# EVGP_Estop_Daugherboard_with_LED.net
KiCad netlist of a schematic drawn in EAGLE
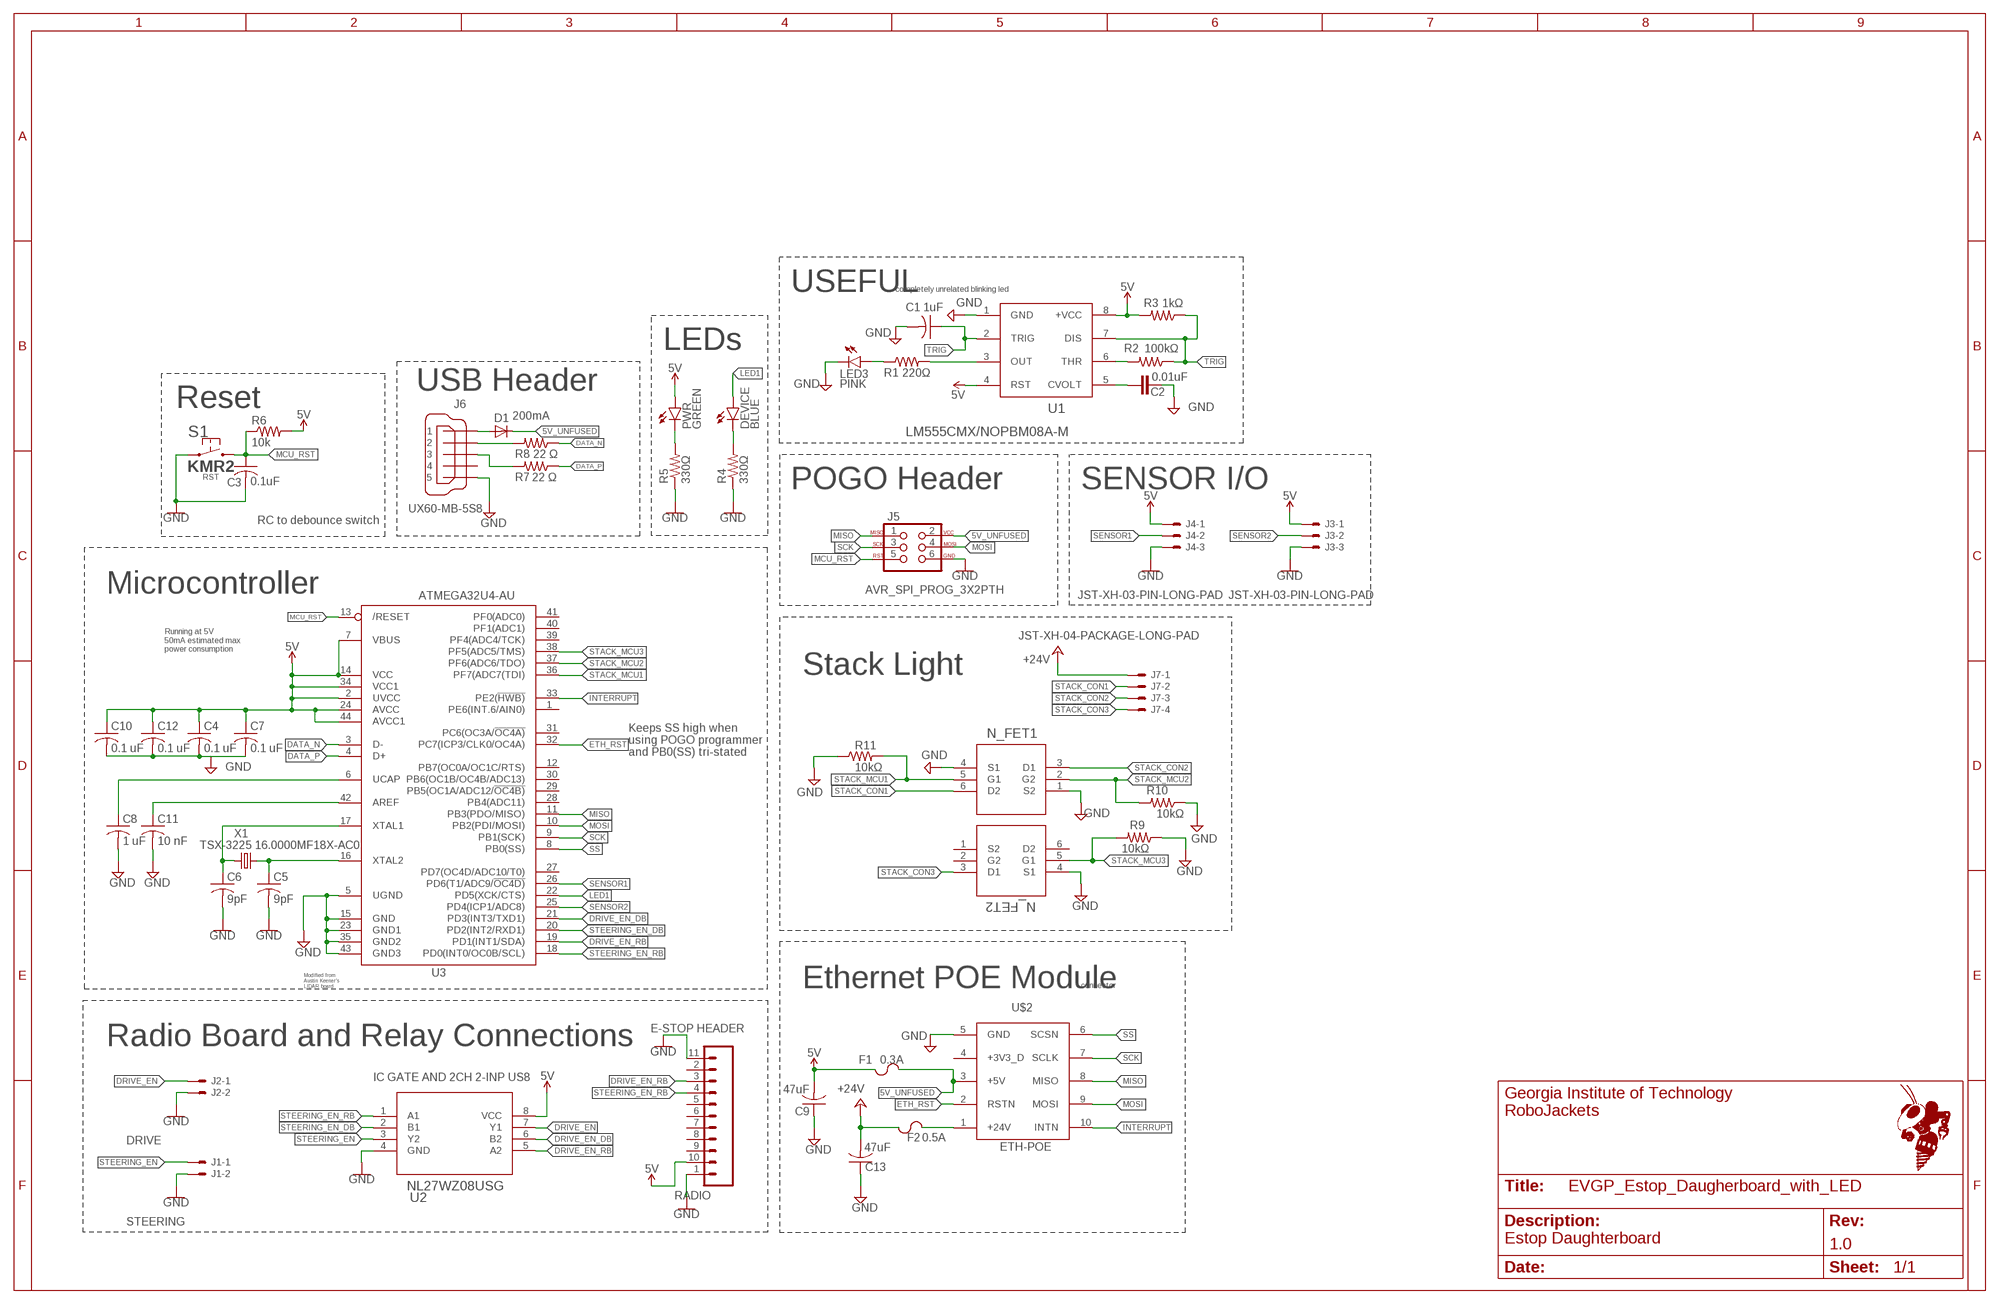
[diagram p0: schematic, sheet 1]

(export (version "E")
  (design (tool "Eeschema 10.0.6"))
  (components
    (comp (ref "C1")
      (value "1uF")
      (footprint "eagle-import:C1206")
      (libsource (lib "eagle-import") (part "C-USC1206"))
    )
    (comp (ref "C2")
      (value "0.01uF")
      (footprint "eagle-import:C0603")
      (libsource (lib "eagle-import") (part "C-EUC0603"))
    )
    (comp (ref "C3")
      (value "0.1uF")
      (footprint "eagle-import:C0603")
      (libsource (lib "eagle-import") (part "C-USC0603"))
    )
    (comp (ref "C4")
      (value "0.1 uF")
      (footprint "eagle-import:C0603")
      (libsource (lib "eagle-import") (part "resistor_348_C-USC0603"))
    )
    (comp (ref "C5")
      (value "9pF")
      (footprint "eagle-import:C0603")
      (libsource (lib "eagle-import") (part "resistor_348_C-USC0603"))
    )
    (comp (ref "C6")
      (value "9pF")
      (footprint "eagle-import:C0603")
      (libsource (lib "eagle-import") (part "resistor_348_C-USC0603"))
    )
    (comp (ref "C7")
      (value "0.1 uF")
      (footprint "eagle-import:C0603")
      (libsource (lib "eagle-import") (part "resistor_348_C-USC0603"))
    )
    (comp (ref "C8")
      (value "1 uF")
      (footprint "eagle-import:C0603")
      (libsource (lib "eagle-import") (part "resistor_348_C-USC0603"))
    )
    (comp (ref "C9")
      (value "47uF")
      (footprint "eagle-import:C1206")
      (libsource (lib "eagle-import") (part "C-USC1206"))
    )
    (comp (ref "C10")
      (value "0.1 uF")
      (footprint "eagle-import:C0603")
      (libsource (lib "eagle-import") (part "resistor_348_C-USC0603"))
    )
    (comp (ref "C11")
      (value "10 nF")
      (footprint "eagle-import:C0603")
      (libsource (lib "eagle-import") (part "resistor_348_C-USC0603"))
    )
    (comp (ref "C12")
      (value "0.1 uF")
      (footprint "eagle-import:C0603")
      (libsource (lib "eagle-import") (part "resistor_348_C-USC0603"))
    )
    (comp (ref "C13")
      (value "47uF")
      (footprint "eagle-import:C1206")
      (libsource (lib "eagle-import") (part "C-USC1206"))
    )
    (comp (ref "D1")
      (value "200mA")
      (footprint "eagle-import:SOD323-R")
      (libsource (lib "eagle-import") (part "DIODE-SOD323-R"))
    )
    (comp (ref "DEVICE")
      (value "BLUE")
      (footprint "eagle-import:CHIP-LED0603")
      (libsource (lib "eagle-import") (part "LEDCHIP-LED0603"))
    )
    (comp (ref "F1")
      (value "0.3A")
      (footprint "eagle-import:F1206")
      (libsource (lib "eagle-import") (part "CHIP_FUSE1206"))
    )
    (comp (ref "F2")
      (value "0.5A")
      (footprint "eagle-import:F1206")
      (libsource (lib "eagle-import") (part "CHIP_FUSE1206"))
    )
    (comp (ref "J1")
      (value "STEERING")
      (footprint "eagle-import:JST-XH-02-PACKAGE-LONG-PAD")
      (libsource (lib "eagle-import") (part "JST-XH-02-PIN-LONG-PAD"))
    )
    (comp (ref "J2")
      (value "DRIVE")
      (footprint "eagle-import:JST-XH-02-PACKAGE-LONG-PAD")
      (libsource (lib "eagle-import") (part "JST-XH-02-PIN-LONG-PAD"))
    )
    (comp (ref "J3")
      (value "JST-XH-03-PIN-LONG-PAD")
      (footprint "eagle-import:JST-XH-03-PACKAGE-LONG-PAD")
      (libsource (lib "eagle-import") (part "JST-XH-03-PIN-LONG-PAD"))
    )
    (comp (ref "J4")
      (value "JST-XH-03-PIN-LONG-PAD")
      (footprint "eagle-import:JST-XH-03-PACKAGE-LONG-PAD")
      (libsource (lib "eagle-import") (part "JST-XH-03-PIN-LONG-PAD"))
    )
    (comp (ref "J5")
      (value "AVR_SPI_PROG_3X2PTH")
      (footprint "eagle-import:2X3")
      (libsource (lib "eagle-import") (part "AVR_SPI_PROG_3X2PTH"))
    )
    (comp (ref "J6")
      (value "UX60-MB-5S8")
      (footprint "eagle-import:UX60-MB-5S8")
      (libsource (lib "eagle-import") (part "UX60-MB-5S?8"))
    )
    (comp (ref "J7")
      (value "JST-XH-04-PACKAGE-LONG-PAD")
      (footprint "eagle-import:JST-XH-04-PACKAGE-LONG-PAD")
      (libsource (lib "eagle-import") (part "JST-XH-04-PIN-LONG-PAD"))
    )
    (comp (ref "LED3")
      (value "PINK")
      (footprint "eagle-import:CHIP-LED0603")
      (libsource (lib "eagle-import") (part "LEDCHIP-LED0603"))
    )
    (comp (ref "PWR")
      (value "GREEN")
      (footprint "eagle-import:CHIP-LED0603")
      (libsource (lib "eagle-import") (part "LEDCHIP-LED0603"))
    )
    (comp (ref "Q1")
      (value "N_FET2")
      (footprint "eagle-import:SOT-363")
      (fields (field (name "MANUFACTURER_PART_NUMBER") "BSS84DW7F"))
      (libsource (lib "eagle-import") (part "BSS84DW-7-F"))
    )
    (comp (ref "Q2")
      (value "N_FET1")
      (footprint "eagle-import:SOT-363")
      (fields (field (name "MANUFACTURER_PART_NUMBER") "BSS84DW7F"))
      (libsource (lib "eagle-import") (part "BSS84DW-7-F"))
    )
    (comp (ref "R1")
      (value "220Ω")
      (footprint "eagle-import:R0603")
      (libsource (lib "eagle-import") (part "R-US_R0603"))
    )
    (comp (ref "R2")
      (value "100kΩ")
      (footprint "eagle-import:R0603")
      (libsource (lib "eagle-import") (part "R-US_R0603"))
    )
    (comp (ref "R3")
      (value "1kΩ")
      (footprint "eagle-import:R0603")
      (libsource (lib "eagle-import") (part "R-US_R0603"))
    )
    (comp (ref "R4")
      (value "330Ω")
      (footprint "eagle-import:R0603")
      (libsource (lib "eagle-import") (part "R-US_R0603"))
    )
    (comp (ref "R5")
      (value "330Ω")
      (footprint "eagle-import:R0603")
      (libsource (lib "eagle-import") (part "R-US_R0603"))
    )
    (comp (ref "R6")
      (value "10k")
      (footprint "eagle-import:R0603")
      (libsource (lib "eagle-import") (part "R-US_R0603"))
    )
    (comp (ref "R7")
      (value "22 Ω")
      (footprint "eagle-import:R0603")
      (libsource (lib "eagle-import") (part "R-US_R0603"))
    )
    (comp (ref "R8")
      (value "22 Ω")
      (footprint "eagle-import:R0603")
      (libsource (lib "eagle-import") (part "R-US_R0603"))
    )
    (comp (ref "R9")
      (value "10kΩ")
      (footprint "eagle-import:R0603")
      (libsource (lib "eagle-import") (part "R-US_R0603"))
    )
    (comp (ref "R10")
      (value "10kΩ")
      (footprint "eagle-import:R0603")
      (libsource (lib "eagle-import") (part "R-US_R0603"))
    )
    (comp (ref "R11")
      (value "10kΩ")
      (footprint "eagle-import:R0603")
      (libsource (lib "eagle-import") (part "R-US_R0603"))
    )
    (comp (ref "RADIO")
      (value "E-STOP HEADER")
      (footprint "eagle-import:RADIO_V1.3")
      (libsource (lib "eagle-import") (part "ESTOP_RADIO"))
    )
    (comp (ref "S1")
      (value "KMR2")
      (footprint "eagle-import:KMR2")
      (fields (field (name "FUNCTION") "Reset") (field (name "FUNCTION_1") "RST"))
      (libsource (lib "eagle-import") (part "KMR2"))
    )
    (comp (ref "U$2")
      (value "ETH-POE")
      (footprint "eagle-import:HDRVR10W64P4000X254_2X5_1016X508X254B")
      (libsource (lib "eagle-import") (part "ETH-POE"))
    )
    (comp (ref "U1")
      (value "LM555CMX/NOPBM08A-M")
      (footprint "eagle-import:M08A-M")
      (fields
        (field (name "MANUFACTURER_PART_NUMBER") "LM555CMX/NOPB")
        (field (name "COPYRIGHT") "Copyright (C) 2018 Accelerated Designs. All rights reserved")
      )
      (libsource (lib "eagle-import") (part "LM555CMX/NOPBM08A-M"))
    )
    (comp (ref "U2")
      (value "NL27WZ08USG")
      (footprint "eagle-import:US8_2P40X2P10")
      (libsource (lib "eagle-import") (part "NL27WZ08USG"))
    )
    (comp (ref "U3")
      (value "ATMEGA32U4-AU")
      (footprint "eagle-import:TQFP44")
      (libsource (lib "eagle-import") (part "ATMEGA32U4-AU"))
    )
    (comp (ref "X1")
      (value "TSX-3225 16.0000MF18X-AC0")
      (footprint "eagle-import:XTAL-3.2X2.5")
      (libsource (lib "eagle-import") (part "XTAL-3.2X2.5"))
    )
  )
  (nets
    (net (code "1") (name "+24V") (class "Default")
      (node (ref "C13") (pin "2") (pinfunction "2_2") (pintype "passive"))
      (node (ref "F2") (pin "1") (pinfunction "1_1") (pintype "bidirectional"))
      (node (ref "J7") (pin "1") (pinfunction "S_1") (pintype "passive"))
    )
    (net (code "2") (name "5V") (class "Default")
      (node (ref "C10") (pin "1") (pinfunction "1_1") (pintype "passive"))
      (node (ref "C12") (pin "1") (pinfunction "1_1") (pintype "passive"))
      (node (ref "C4") (pin "1") (pinfunction "1_1") (pintype "passive"))
      (node (ref "C7") (pin "1") (pinfunction "1_1") (pintype "passive"))
      (node (ref "C9") (pin "2") (pinfunction "2_2") (pintype "passive"))
      (node (ref "F1") (pin "1") (pinfunction "1_1") (pintype "bidirectional"))
      (node (ref "J3") (pin "1") (pinfunction "S_1") (pintype "passive"))
      (node (ref "J4") (pin "1") (pinfunction "S_1") (pintype "passive"))
      (node (ref "PWR") (pin "A") (pinfunction "A_A") (pintype "passive"))
      (node (ref "R3") (pin "2") (pinfunction "2_2") (pintype "passive"))
      (node (ref "R6") (pin "2") (pinfunction "2_2") (pintype "passive"))
      (node (ref "RADIO") (pin "10") (pinfunction "5V_10") (pintype "passive"))
      (node (ref "U1") (pin "4") (pinfunction "RST_4") (pintype "input"))
      (node (ref "U1") (pin "8") (pinfunction "+VCC_8") (pintype "power_in"))
      (node (ref "U2") (pin "8") (pinfunction "VCC_8") (pintype "power_in"))
      (node (ref "U3") (pin "14") (pinfunction "VCC_14") (pintype "bidirectional"))
      (node (ref "U3") (pin "2") (pinfunction "UVCC_2") (pintype "bidirectional"))
      (node (ref "U3") (pin "24") (pinfunction "AVCC_24") (pintype "bidirectional"))
      (node (ref "U3") (pin "34") (pinfunction "VCC1_34") (pintype "bidirectional"))
      (node (ref "U3") (pin "44") (pinfunction "AVCC1_44") (pintype "bidirectional"))
      (node (ref "U3") (pin "7") (pinfunction "VBUS_7") (pintype "bidirectional"))
    )
    (net (code "3") (name "5V_UNFUSED") (class "Default")
      (node (ref "D1") (pin "C") (pinfunction "C_C") (pintype "passive"))
      (node (ref "F1") (pin "2") (pinfunction "2_2") (pintype "bidirectional"))
      (node (ref "J5") (pin "2") (pinfunction "2_2") (pintype "passive"))
      (node (ref "U$2") (pin "3") (pinfunction "+5V_3") (pintype "bidirectional"))
    )
    (net (code "4") (name "DATA_N") (class "Default")
      (node (ref "R8") (pin "1") (pinfunction "1_1") (pintype "passive"))
      (node (ref "U3") (pin "3") (pinfunction "D-_3") (pintype "bidirectional"))
    )
    (net (code "5") (name "DATA_P") (class "Default")
      (node (ref "R7") (pin "1") (pinfunction "1_1") (pintype "passive"))
      (node (ref "U3") (pin "4") (pinfunction "D+_4") (pintype "bidirectional"))
    )
    (net (code "6") (name "DRIVE_EN") (class "Default")
      (node (ref "J2") (pin "1") (pinfunction "S_1") (pintype "passive"))
      (node (ref "U2") (pin "7") (pinfunction "Y1_7") (pintype "output"))
    )
    (net (code "7") (name "DRIVE_EN_DB") (class "Default")
      (node (ref "U2") (pin "6") (pinfunction "B2_6") (pintype "input"))
      (node (ref "U3") (pin "21") (pinfunction "PD3(INT3/TXD1)_21") (pintype "bidirectional"))
    )
    (net (code "8") (name "DRIVE_EN_RB") (class "Default")
      (node (ref "RADIO") (pin "3") (pinfunction "D1_3") (pintype "passive"))
      (node (ref "U2") (pin "5") (pinfunction "A2_5") (pintype "input"))
      (node (ref "U3") (pin "19") (pinfunction "PD1(INT1/SDA)_19") (pintype "bidirectional"))
    )
    (net (code "9") (name "ETH_RST") (class "Default")
      (node (ref "U$2") (pin "2") (pinfunction "RSTN_2") (pintype "bidirectional"))
      (node (ref "U3") (pin "32") (pinfunction "PC7(ICP3/CLK0/OC4A)_32") (pintype "bidirectional"))
    )
    (net (code "10") (name "GND") (class "Default")
      (node (ref "C1") (pin "2") (pinfunction "2_2") (pintype "passive"))
      (node (ref "C10") (pin "2") (pinfunction "2_2") (pintype "passive"))
      (node (ref "C11") (pin "2") (pinfunction "2_2") (pintype "passive"))
      (node (ref "C12") (pin "2") (pinfunction "2_2") (pintype "passive"))
      (node (ref "C13") (pin "1") (pinfunction "1_1") (pintype "passive"))
      (node (ref "C2") (pin "2") (pinfunction "2_2") (pintype "passive"))
      (node (ref "C3") (pin "2") (pinfunction "2_2") (pintype "passive"))
      (node (ref "C4") (pin "2") (pinfunction "2_2") (pintype "passive"))
      (node (ref "C5") (pin "2") (pinfunction "2_2") (pintype "passive"))
      (node (ref "C6") (pin "2") (pinfunction "2_2") (pintype "passive"))
      (node (ref "C7") (pin "2") (pinfunction "2_2") (pintype "passive"))
      (node (ref "C8") (pin "2") (pinfunction "2_2") (pintype "passive"))
      (node (ref "C9") (pin "1") (pinfunction "1_1") (pintype "passive"))
      (node (ref "J1") (pin "2") (pinfunction "S_2") (pintype "passive"))
      (node (ref "J2") (pin "2") (pinfunction "S_2") (pintype "passive"))
      (node (ref "J3") (pin "3") (pinfunction "S_3") (pintype "passive"))
      (node (ref "J4") (pin "3") (pinfunction "S_3") (pintype "passive"))
      (node (ref "J5") (pin "6") (pinfunction "6_6") (pintype "passive"))
      (node (ref "J6") (pin "5") (pinfunction "5_5") (pintype "passive"))
      (node (ref "LED3") (pin "C") (pinfunction "C_C") (pintype "passive"))
      (node (ref "Q1") (pin "4") (pinfunction "S1_4") (pintype "passive"))
      (node (ref "Q2") (pin "1") (pinfunction "S2_1") (pintype "passive"))
      (node (ref "Q2") (pin "4") (pinfunction "S1_4") (pintype "passive"))
      (node (ref "R10") (pin "1") (pinfunction "1_1") (pintype "passive"))
      (node (ref "R11") (pin "1") (pinfunction "1_1") (pintype "passive"))
      (node (ref "R4") (pin "1") (pinfunction "1_1") (pintype "passive"))
      (node (ref "R5") (pin "1") (pinfunction "1_1") (pintype "passive"))
      (node (ref "R9") (pin "1") (pinfunction "1_1") (pintype "passive"))
      (node (ref "RADIO") (pin "1") (pinfunction "GND_1") (pintype "passive"))
      (node (ref "RADIO") (pin "11") (pinfunction "GND_11") (pintype "passive"))
      (node (ref "S1") (pin "1.1") (pinfunction "1_1.1") (pintype "passive"))
      (node (ref "S1") (pin "1.2") (pinfunction "1_1.2") (pintype "passive"))
      (node (ref "U$2") (pin "5") (pinfunction "GND_5") (pintype "bidirectional"))
      (node (ref "U1") (pin "1") (pinfunction "GND_1") (pintype "power_in"))
      (node (ref "U2") (pin "4") (pinfunction "GND_4") (pintype "power_in"))
      (node (ref "U3") (pin "15") (pinfunction "GND_15") (pintype "bidirectional"))
      (node (ref "U3") (pin "23") (pinfunction "GND1_23") (pintype "bidirectional"))
      (node (ref "U3") (pin "35") (pinfunction "GND2_35") (pintype "bidirectional"))
      (node (ref "U3") (pin "43") (pinfunction "GND3_43") (pintype "bidirectional"))
      (node (ref "U3") (pin "5") (pinfunction "UGND_5") (pintype "bidirectional"))
    )
    (net (code "11") (name "INTERRUPT") (class "Default")
      (node (ref "U$2") (pin "10") (pinfunction "INTN_10") (pintype "bidirectional"))
      (node (ref "U3") (pin "33") (pinfunction "PE2(~{HWB})_33") (pintype "bidirectional"))
    )
    (net (code "12") (name "LED1") (class "Default")
      (node (ref "DEVICE") (pin "A") (pinfunction "A_A") (pintype "passive"))
      (node (ref "U3") (pin "22") (pinfunction "PD5(XCK/CTS)_22") (pintype "bidirectional"))
    )
    (net (code "13") (name "MCU_RST") (class "Default")
      (node (ref "C3") (pin "1") (pinfunction "1_1") (pintype "passive"))
      (node (ref "J5") (pin "5") (pinfunction "5_5") (pintype "passive"))
      (node (ref "R6") (pin "1") (pinfunction "1_1") (pintype "passive"))
      (node (ref "S1") (pin "2.1") (pinfunction "2_2.1") (pintype "passive"))
      (node (ref "S1") (pin "2.2") (pinfunction "2_2.2") (pintype "passive"))
      (node (ref "U3") (pin "13") (pinfunction "/RESET_13") (pintype "bidirectional"))
    )
    (net (code "14") (name "MISO") (class "Default")
      (node (ref "J5") (pin "1") (pinfunction "1_1") (pintype "passive"))
      (node (ref "U$2") (pin "8") (pinfunction "MISO_8") (pintype "bidirectional"))
      (node (ref "U3") (pin "11") (pinfunction "PB3(PDO/MISO)_11") (pintype "bidirectional"))
    )
    (net (code "15") (name "MOSI") (class "Default")
      (node (ref "J5") (pin "4") (pinfunction "4_4") (pintype "passive"))
      (node (ref "U$2") (pin "9") (pinfunction "MOSI_9") (pintype "bidirectional"))
      (node (ref "U3") (pin "10") (pinfunction "PB2(PDI/MOSI)_10") (pintype "bidirectional"))
    )
    (net (code "16") (name "Net-(D1-PadA)") (class "Default")
      (node (ref "D1") (pin "A") (pinfunction "A_A") (pintype "passive"))
      (node (ref "J6") (pin "1") (pinfunction "1_1") (pintype "passive"))
    )
    (net (code "17") (name "Net-(DEVICE-PadC)") (class "Default")
      (node (ref "DEVICE") (pin "C") (pinfunction "C_C") (pintype "passive"))
      (node (ref "R4") (pin "2") (pinfunction "2_2") (pintype "passive"))
    )
    (net (code "18") (name "Net-(J6-Pad2)") (class "Default")
      (node (ref "J6") (pin "2") (pinfunction "2_2") (pintype "passive"))
      (node (ref "R8") (pin "2") (pinfunction "2_2") (pintype "passive"))
    )
    (net (code "19") (name "Net-(J6-Pad3)") (class "Default")
      (node (ref "J6") (pin "3") (pinfunction "3_3") (pintype "passive"))
      (node (ref "R7") (pin "2") (pinfunction "2_2") (pintype "passive"))
    )
    (net (code "20") (name "Net-(LED3-PadA)") (class "Default")
      (node (ref "LED3") (pin "A") (pinfunction "A_A") (pintype "passive"))
      (node (ref "R1") (pin "1") (pinfunction "1_1") (pintype "passive"))
    )
    (net (code "21") (name "Net-(PWR-PadC)") (class "Default")
      (node (ref "PWR") (pin "C") (pinfunction "C_C") (pintype "passive"))
      (node (ref "R5") (pin "2") (pinfunction "2_2") (pintype "passive"))
    )
    (net (code "22") (name "Net-(U$2-+24V)") (class "Default")
      (node (ref "F2") (pin "2") (pinfunction "2_2") (pintype "bidirectional"))
      (node (ref "U$2") (pin "1") (pinfunction "+24V_1") (pintype "bidirectional"))
    )
    (net (code "23") (name "Net-(U1-CVOLT)") (class "Default")
      (node (ref "C2") (pin "1") (pinfunction "1_1") (pintype "passive"))
      (node (ref "U1") (pin "5") (pinfunction "CVOLT_5") (pintype "passive"))
    )
    (net (code "24") (name "Net-(U1-OUT)") (class "Default")
      (node (ref "R1") (pin "2") (pinfunction "2_2") (pintype "passive"))
      (node (ref "U1") (pin "3") (pinfunction "OUT_3") (pintype "output"))
    )
    (net (code "25") (name "Net-(U1-THR)") (class "Default")
      (node (ref "R2") (pin "2") (pinfunction "2_2") (pintype "passive"))
      (node (ref "U1") (pin "6") (pinfunction "THR_6") (pintype "input"))
    )
    (net (code "26") (name "Net-(U3-AREF)") (class "Default")
      (node (ref "C11") (pin "1") (pinfunction "1_1") (pintype "passive"))
      (node (ref "U3") (pin "42") (pinfunction "AREF_42") (pintype "bidirectional"))
    )
    (net (code "27") (name "Net-(U3-UCAP)") (class "Default")
      (node (ref "C8") (pin "1") (pinfunction "1_1") (pintype "passive"))
      (node (ref "U3") (pin "6") (pinfunction "UCAP_6") (pintype "bidirectional"))
    )
    (net (code "28") (name "Net-(U3-XTAL1)") (class "Default")
      (node (ref "C6") (pin "1") (pinfunction "1_1") (pintype "passive"))
      (node (ref "U3") (pin "17") (pinfunction "XTAL1_17") (pintype "bidirectional"))
      (node (ref "X1") (pin "1") (pinfunction "1_1") (pintype "passive"))
    )
    (net (code "29") (name "Net-(U3-XTAL2)") (class "Default")
      (node (ref "C5") (pin "1") (pinfunction "1_1") (pintype "passive"))
      (node (ref "U3") (pin "16") (pinfunction "XTAL2_16") (pintype "bidirectional"))
      (node (ref "X1") (pin "3") (pinfunction "2_3") (pintype "passive"))
    )
    (net (code "30") (name "SCK") (class "Default")
      (node (ref "J5") (pin "3") (pinfunction "3_3") (pintype "passive"))
      (node (ref "U$2") (pin "7") (pinfunction "SCLK_7") (pintype "bidirectional"))
      (node (ref "U3") (pin "9") (pinfunction "PB1(SCK)_9") (pintype "bidirectional"))
    )
    (net (code "31") (name "SENSOR1") (class "Default")
      (node (ref "J4") (pin "2") (pinfunction "S_2") (pintype "passive"))
      (node (ref "U3") (pin "26") (pinfunction "PD6(T1/ADC9/~{OC4D})_26") (pintype "bidirectional"))
    )
    (net (code "32") (name "SENSOR2") (class "Default")
      (node (ref "J3") (pin "2") (pinfunction "S_2") (pintype "passive"))
      (node (ref "U3") (pin "25") (pinfunction "PD4(ICP1/ADC8)_25") (pintype "bidirectional"))
    )
    (net (code "33") (name "SS") (class "Default")
      (node (ref "U$2") (pin "6") (pinfunction "SCSN_6") (pintype "bidirectional"))
      (node (ref "U3") (pin "8") (pinfunction "PB0(SS)_8") (pintype "bidirectional"))
    )
    (net (code "34") (name "STACK_CON1") (class "Default")
      (node (ref "J7") (pin "2") (pinfunction "S_2") (pintype "passive"))
      (node (ref "Q2") (pin "6") (pinfunction "D2_6") (pintype "passive"))
    )
    (net (code "35") (name "STACK_CON2") (class "Default")
      (node (ref "J7") (pin "3") (pinfunction "S_3") (pintype "passive"))
      (node (ref "Q2") (pin "3") (pinfunction "D1_3") (pintype "passive"))
    )
    (net (code "36") (name "STACK_CON3") (class "Default")
      (node (ref "J7") (pin "4") (pinfunction "S_4") (pintype "passive"))
      (node (ref "Q1") (pin "3") (pinfunction "D1_3") (pintype "passive"))
    )
    (net (code "37") (name "STACK_MCU1") (class "Default")
      (node (ref "Q2") (pin "5") (pinfunction "G1_5") (pintype "passive"))
      (node (ref "R11") (pin "2") (pinfunction "2_2") (pintype "passive"))
      (node (ref "U3") (pin "36") (pinfunction "PF7(ADC7(TDI)_36") (pintype "bidirectional"))
    )
    (net (code "38") (name "STACK_MCU2") (class "Default")
      (node (ref "Q2") (pin "2") (pinfunction "G2_2") (pintype "passive"))
      (node (ref "R10") (pin "2") (pinfunction "2_2") (pintype "passive"))
      (node (ref "U3") (pin "37") (pinfunction "PF6(ADC6/TDO)_37") (pintype "bidirectional"))
    )
    (net (code "39") (name "STACK_MCU3") (class "Default")
      (node (ref "Q1") (pin "5") (pinfunction "G1_5") (pintype "passive"))
      (node (ref "R9") (pin "2") (pinfunction "2_2") (pintype "passive"))
      (node (ref "U3") (pin "38") (pinfunction "PF5(ADC5/TMS)_38") (pintype "bidirectional"))
    )
    (net (code "40") (name "STEERING_EN") (class "Default")
      (node (ref "J1") (pin "1") (pinfunction "S_1") (pintype "passive"))
      (node (ref "U2") (pin "3") (pinfunction "Y2_3") (pintype "output"))
    )
    (net (code "41") (name "STEERING_EN_DB") (class "Default")
      (node (ref "U2") (pin "2") (pinfunction "B1_2") (pintype "input"))
      (node (ref "U3") (pin "20") (pinfunction "PD2(INT2/RXD1)_20") (pintype "bidirectional"))
    )
    (net (code "42") (name "STEERING_EN_RB") (class "Default")
      (node (ref "RADIO") (pin "4") (pinfunction "D2_4") (pintype "passive"))
      (node (ref "U2") (pin "1") (pinfunction "A1_1") (pintype "input"))
      (node (ref "U3") (pin "18") (pinfunction "PD0(INT0/OC0B/SCL)_18") (pintype "bidirectional"))
    )
    (net (code "43") (name "TRIG") (class "Default")
      (node (ref "C1") (pin "1") (pinfunction "1_1") (pintype "passive"))
      (node (ref "R2") (pin "1") (pinfunction "1_1") (pintype "passive"))
      (node (ref "R3") (pin "1") (pinfunction "1_1") (pintype "passive"))
      (node (ref "U1") (pin "2") (pinfunction "TRIG_2") (pintype "input"))
      (node (ref "U1") (pin "7") (pinfunction "DIS_7") (pintype "passive"))
    )
    (net (code "44") (name "unconnected-(J6-Pad4)") (class "Default")
      (node (ref "J6") (pin "4") (pinfunction "4_4") (pintype "passive"))
    )
    (net (code "45") (name "unconnected-(Q1-D2-Pad6)") (class "Default")
      (node (ref "Q1") (pin "6") (pinfunction "D2_6") (pintype "passive"))
    )
    (net (code "46") (name "unconnected-(Q1-G2-Pad2)") (class "Default")
      (node (ref "Q1") (pin "2") (pinfunction "G2_2") (pintype "passive"))
    )
    (net (code "47") (name "unconnected-(Q1-S2-Pad1)") (class "Default")
      (node (ref "Q1") (pin "1") (pinfunction "S2_1") (pintype "passive"))
    )
    (net (code "48") (name "unconnected-(RADIO-D3-Pad5)") (class "Default")
      (node (ref "RADIO") (pin "5") (pinfunction "D3_5") (pintype "passive"))
    )
    (net (code "49") (name "unconnected-(RADIO-D4-Pad6)") (class "Default")
      (node (ref "RADIO") (pin "6") (pinfunction "D4_6") (pintype "passive"))
    )
    (net (code "50") (name "unconnected-(RADIO-D5-Pad7)") (class "Default")
      (node (ref "RADIO") (pin "7") (pinfunction "D5_7") (pintype "passive"))
    )
    (net (code "51") (name "unconnected-(RADIO-D6-Pad8)") (class "Default")
      (node (ref "RADIO") (pin "8") (pinfunction "D6_8") (pintype "passive"))
    )
    (net (code "52") (name "unconnected-(RADIO-D7-Pad9)") (class "Default")
      (node (ref "RADIO") (pin "9") (pinfunction "D7_9") (pintype "passive"))
    )
    (net (code "53") (name "unconnected-(RADIO-RST-Pad2)") (class "Default")
      (node (ref "RADIO") (pin "2") (pinfunction "RST_2") (pintype "passive"))
    )
    (net (code "54") (name "unconnected-(U$2-+3V3_D-Pad4)") (class "Default")
      (node (ref "U$2") (pin "4") (pinfunction "+3V3_D_4") (pintype "bidirectional"))
    )
    (net (code "55") (name "unconnected-(U3-PB4(ADC11)-Pad28)") (class "Default")
      (node (ref "U3") (pin "28") (pinfunction "PB4(ADC11)_28") (pintype "bidirectional"))
    )
    (net (code "56") (name "unconnected-(U3-PB5(OC1A{slash}ADC12{slash}~{OC4B})-Pad29)") (class "Default")
      (node (ref "U3") (pin "29") (pinfunction "PB5(OC1A/ADC12/~{OC4B})_29") (pintype "bidirectional"))
    )
    (net (code "57") (name "unconnected-(U3-PB6(OC1B{slash}OC4B{slash}ADC13)-Pad30)") (class "Default")
      (node (ref "U3") (pin "30") (pinfunction "PB6(OC1B/OC4B/ADC13)_30") (pintype "bidirectional"))
    )
    (net (code "58") (name "unconnected-(U3-PB7(OC0A{slash}OC1C{slash}RTS)-Pad12)") (class "Default")
      (node (ref "U3") (pin "12") (pinfunction "PB7(OC0A/OC1C/RTS)_12") (pintype "bidirectional"))
    )
    (net (code "59") (name "unconnected-(U3-PC6(OC3A{slash}~{OC4A})-Pad31)") (class "Default")
      (node (ref "U3") (pin "31") (pinfunction "PC6(OC3A/~{OC4A})_31") (pintype "bidirectional"))
    )
    (net (code "60") (name "unconnected-(U3-PD7(OC4D{slash}ADC10{slash}T0)-Pad27)") (class "Default")
      (node (ref "U3") (pin "27") (pinfunction "PD7(OC4D/ADC10/T0)_27") (pintype "bidirectional"))
    )
    (net (code "61") (name "unconnected-(U3-PE6(INT.6{slash}AIN0)-Pad1)") (class "Default")
      (node (ref "U3") (pin "1") (pinfunction "PE6(INT.6/AIN0)_1") (pintype "bidirectional"))
    )
    (net (code "62") (name "unconnected-(U3-PF0(ADC0)-Pad41)") (class "Default")
      (node (ref "U3") (pin "41") (pinfunction "PF0(ADC0)_41") (pintype "bidirectional"))
    )
    (net (code "63") (name "unconnected-(U3-PF1(ADC1)-Pad40)") (class "Default")
      (node (ref "U3") (pin "40") (pinfunction "PF1(ADC1)_40") (pintype "bidirectional"))
    )
    (net (code "64") (name "unconnected-(U3-PF4(ADC4{slash}TCK)-Pad39)") (class "Default")
      (node (ref "U3") (pin "39") (pinfunction "PF4(ADC4/TCK)_39") (pintype "bidirectional"))
    )
  )
)
